# US_EPS_RBF.net
KiCad netlist of a schematic drawn in Altium Designer
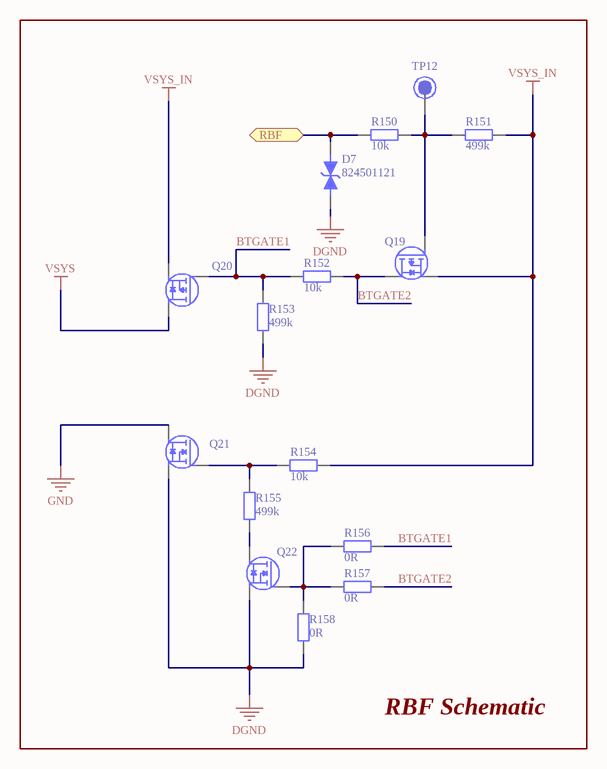
[diagram p0: US_EPS_RBF.SchDoc]

(export (version "E")
  (design (tool "Eeschema 10.0.6"))
  (components
    (comp (ref "D7")
      (value "824501121")
      (footprint "alfasat_lib_eps:DIOM4227X25N")
      (description "TVS DIODE 12V 19.9V DO214AC")
      (fields (field (name "MANUFACTURER") "Wurth Electronics Inc."))
      (libsource (lib "alfasat_lib_eps") (part "824501121_TVS"))
    )
    (comp (ref "Q19")
      (value "SISH625DN-T1-GE3")
      (footprint "SISH625DN")
      (description "P-Channel 30V 17.3A (Ta), 35A (Tc) 3.7W (Ta), 52W (Tc) Surface Mount PowerPAK® 1212-8SH")
      (fields (field (name "MANUFACTURER") "Vishay Siliconix"))
      (libsource (lib "alfasat_lib_eps") (part "SISH625DN-T1"))
    )
    (comp (ref "Q20")
      (value "SISH625DN-T1-GE3")
      (footprint "SISH625DN")
      (description "P-Channel 30V 17.3A (Ta), 35A (Tc) 3.7W (Ta), 52W (Tc) Surface Mount PowerPAK® 1212-8SH")
      (fields (field (name "MANUFACTURER") "Vishay Siliconix"))
      (libsource (lib "alfasat_lib_eps") (part "SISH625DN-T1"))
    )
    (comp (ref "Q21")
      (value "SISA14DN-T1-GE3")
      (footprint "SISA14DN")
      (description "N-Channel 30V 20A (Tc) 3.57W (Ta), 26.5W (Tc) Surface Mount PowerPAK® 1212-8")
      (fields (field (name "MANUFACTURER") "Vishay Siliconix"))
      (libsource (lib "alfasat_lib_eps") (part "SiSA14DN"))
    )
    (comp (ref "Q22")
      (value "SISA14DN-T1-GE3")
      (footprint "SISA14DN")
      (description "N-Channel 30V 20A (Tc) 3.57W (Ta), 26.5W (Tc) Surface Mount PowerPAK® 1212-8")
      (fields (field (name "MANUFACTURER") "Vishay Siliconix"))
      (libsource (lib "alfasat_lib_eps") (part "SiSA14DN"))
    )
    (comp (ref "R150")
      (value "10k")
      (footprint "C0603_IPC_HD")
      (description "RES 10K OHM 1% 1/10W 0603")
      (fields
        (field (name "MANUFACTURER") "Stackpole Electronics Inc")
        (field (name "MANUFACTURER PART NUMBER") "RMCF0603FT10K0")
      )
      (libsource (lib "alfasat_lib_eps") (part "CR0603-JW-10k"))
    )
    (comp (ref "R151")
      (value "499k")
      (footprint "C0603_IPC_HD")
      (description "RES 499K OHM 1% 1/10W 0603")
      (fields
        (field (name "MANUFACTURER") "Stackpole Electronics Inc")
        (field (name "MANUFACTURER PART NUMBER") "RMCF0603FT499K")
      )
      (libsource (lib "") (part "CR0603-JW-499K_1"))
    )
    (comp (ref "R152")
      (value "10k")
      (footprint "C0603_IPC_HD")
      (description "RES 10K OHM 1% 1/10W 0603")
      (fields
        (field (name "MANUFACTURER") "Stackpole Electronics Inc")
        (field (name "MANUFACTURER PART NUMBER") "RMCF0603FT10K0")
      )
      (libsource (lib "alfasat_lib_eps") (part "CR0603-JW-10k"))
    )
    (comp (ref "R153")
      (value "499k")
      (footprint "C0603_IPC_HD")
      (description "RES 499K OHM 1% 1/10W 0603")
      (fields
        (field (name "MANUFACTURER") "Stackpole Electronics Inc")
        (field (name "MANUFACTURER PART NUMBER") "RMCF0603FT499K")
      )
      (libsource (lib "alfasat_lib_eps") (part "CR0603-JW-499K"))
    )
    (comp (ref "R154")
      (value "10k")
      (footprint "C0603_IPC_HD")
      (description "RES 10K OHM 1% 1/10W 0603")
      (fields
        (field (name "MANUFACTURER") "Stackpole Electronics Inc")
        (field (name "MANUFACTURER PART NUMBER") "RMCF0603FT10K0")
      )
      (libsource (lib "alfasat_lib_eps") (part "CR0603-JW-10k"))
    )
    (comp (ref "R155")
      (value "499k")
      (footprint "C0603_IPC_HD")
      (description "RES 499K OHM 1% 1/10W 0603")
      (fields
        (field (name "MANUFACTURER") "Stackpole Electronics Inc")
        (field (name "MANUFACTURER PART NUMBER") "RMCF0603FT499K")
      )
      (libsource (lib "alfasat_lib_eps") (part "CR0603-JW-499K"))
    )
    (comp (ref "R156")
      (value "0R")
      (footprint "R0603_IPC_MD")
      (description "RES SMD 0 OHM JUMPER 1/10W 0603")
      (fields
        (field (name "MANUFACTURER") "Bourns Inc.")
        (field (name "MANUFACTURER PART NUMBER") "CR0603-J/-000ELF")
      )
      (libsource (lib "alfasat_lib") (part "CR0603-J/-000ELF"))
    )
    (comp (ref "R157")
      (value "0R")
      (footprint "R0603_IPC_MD")
      (description "RES SMD 0 OHM JUMPER 1/10W 0603")
      (fields
        (field (name "MANUFACTURER") "Bourns Inc.")
        (field (name "MANUFACTURER PART NUMBER") "CR0603-J/-000ELF")
      )
      (libsource (lib "alfasat_lib") (part "CR0603-J/-000ELF"))
    )
    (comp (ref "R158")
      (value "0R")
      (footprint "R0603_IPC_MD")
      (description "RES SMD 0 OHM JUMPER 1/10W 0603")
      (fields
        (field (name "MANUFACTURER") "Bourns Inc.")
        (field (name "MANUFACTURER PART NUMBER") "CR0603-J/-000ELF")
      )
      (libsource (lib "") (part "CR0603-J/-000ELF_1"))
    )
    (comp (ref "TP12")
      (value "Test Point")
      (footprint "TestPoint_1M5")
      (libsource (lib "alfasat_lib") (part "TP"))
    )
  )
  (nets
    (net (code "1") (name "/BTGATE1") (class "Default")
      (node (ref "Q20") (pin "2") (pinfunction "G_2") (pintype "passive"))
      (node (ref "R152") (pin "1") (pinfunction "1_1") (pintype "passive"))
      (node (ref "R153") (pin "2") (pinfunction "2_2") (pintype "passive"))
      (node (ref "R156") (pin "2") (pinfunction "2_2") (pintype "passive"))
    )
    (net (code "2") (name "/BTGATE2") (class "Default")
      (node (ref "Q19") (pin "3") (pinfunction "D_3") (pintype "passive"))
      (node (ref "R152") (pin "2") (pinfunction "2_2") (pintype "passive"))
      (node (ref "R157") (pin "2") (pinfunction "2_2") (pintype "passive"))
    )
    (net (code "3") (name "/RBF") (class "Default")
      (node (ref "D7") (pin "2") (pinfunction "2_2") (pintype "passive"))
      (node (ref "R150") (pin "1") (pinfunction "1_1") (pintype "passive"))
    )
    (net (code "4") (name "DGND") (class "Default")
      (node (ref "D7") (pin "1") (pinfunction "1_1") (pintype "passive"))
      (node (ref "Q21") (pin "1") (pinfunction "S_1") (pintype "passive"))
      (node (ref "Q22") (pin "1") (pinfunction "S_1") (pintype "passive"))
      (node (ref "R153") (pin "1") (pinfunction "1_1") (pintype "passive"))
      (node (ref "R158") (pin "1") (pinfunction "1_1") (pintype "passive"))
    )
    (net (code "5") (name "GND") (class "Default")
      (node (ref "Q21") (pin "3") (pinfunction "D_3") (pintype "passive"))
    )
    (net (code "6") (name "Net-(Q19-G)") (class "Default")
      (node (ref "Q19") (pin "2") (pinfunction "G_2") (pintype "passive"))
      (node (ref "R150") (pin "2") (pinfunction "2_2") (pintype "passive"))
      (node (ref "R151") (pin "2") (pinfunction "2_2") (pintype "passive"))
      (node (ref "TP12") (pin "0") (pinfunction "0_0") (pintype "passive"))
    )
    (net (code "7") (name "Net-(Q21-G)") (class "Default")
      (node (ref "Q21") (pin "2") (pinfunction "G_2") (pintype "passive"))
      (node (ref "R154") (pin "1") (pinfunction "1_1") (pintype "passive"))
      (node (ref "R155") (pin "2") (pinfunction "2_2") (pintype "passive"))
    )
    (net (code "8") (name "Net-(Q22-D)") (class "Default")
      (node (ref "Q22") (pin "3") (pinfunction "D_3") (pintype "passive"))
      (node (ref "R155") (pin "1") (pinfunction "1_1") (pintype "passive"))
    )
    (net (code "9") (name "Net-(Q22-G)") (class "Default")
      (node (ref "Q22") (pin "2") (pinfunction "G_2") (pintype "passive"))
      (node (ref "R156") (pin "1") (pinfunction "1_1") (pintype "passive"))
      (node (ref "R157") (pin "1") (pinfunction "1_1") (pintype "passive"))
      (node (ref "R158") (pin "2") (pinfunction "2_2") (pintype "passive"))
    )
    (net (code "10") (name "VSYS") (class "Default")
      (node (ref "Q20") (pin "3") (pinfunction "D_3") (pintype "passive"))
    )
    (net (code "11") (name "VSYS_IN") (class "Default")
      (node (ref "Q19") (pin "1") (pinfunction "S_1") (pintype "passive"))
      (node (ref "Q20") (pin "1") (pinfunction "S_1") (pintype "passive"))
      (node (ref "R151") (pin "1") (pinfunction "1_1") (pintype "passive"))
      (node (ref "R154") (pin "2") (pinfunction "2_2") (pintype "passive"))
    )
  )
)
